# nerdstern.net
KiCad netlist of a schematic drawn in EAGLE
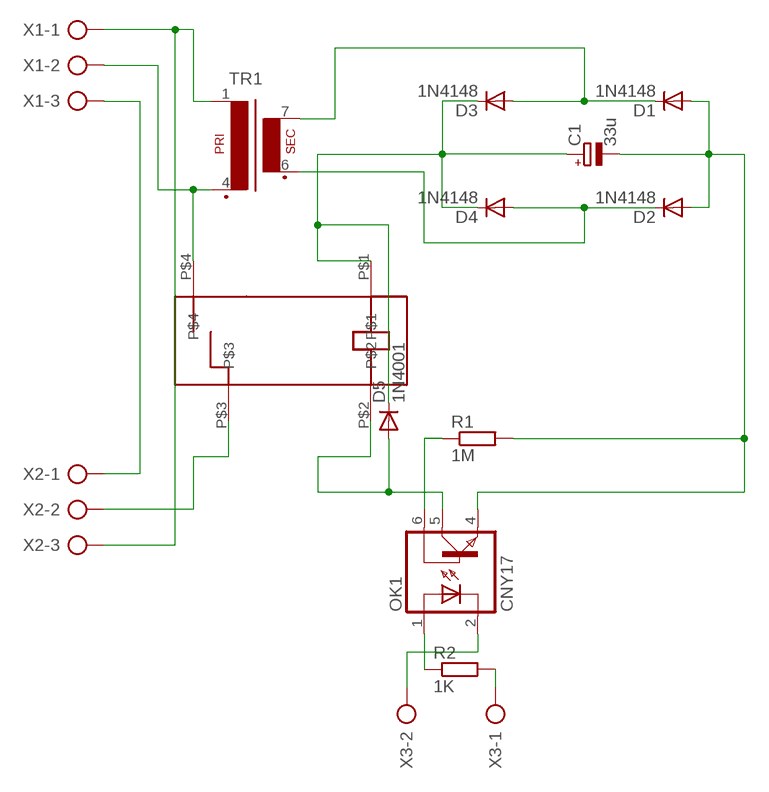
[diagram p0: schematic, sheet 1]

(export (version "E")
  (design (tool "Eeschema 10.0.6"))
  (components
    (comp (ref "C1")
      (value "33u")
      (footprint "eagle-import:E2-5")
      (libsource (lib "eagle-import") (part "CPOL-EUE2-5"))
    )
    (comp (ref "D1")
      (value "1N4148")
      (footprint "eagle-import:DO35-7")
      (libsource (lib "eagle-import") (part "1N4148DO35-7"))
    )
    (comp (ref "D2")
      (value "1N4148")
      (footprint "eagle-import:DO35-7")
      (libsource (lib "eagle-import") (part "1N4148DO35-7"))
    )
    (comp (ref "D3")
      (value "1N4148")
      (footprint "eagle-import:DO35-7")
      (libsource (lib "eagle-import") (part "1N4148DO35-7"))
    )
    (comp (ref "D4")
      (value "1N4148")
      (footprint "eagle-import:DO35-7")
      (libsource (lib "eagle-import") (part "1N4148DO35-7"))
    )
    (comp (ref "D5")
      (value "1N4001")
      (footprint "eagle-import:DO35-7")
      (libsource (lib "eagle-import") (part "1N4148DO35-7"))
    )
    (comp (ref "OK1")
      (value "CNY17")
      (footprint "eagle-import:DIL06")
      (fields (field (name "MPN") "CNY17-1"))
      (libsource (lib "eagle-import") (part "CNY17"))
    )
    (comp (ref "R1")
      (value "1M")
      (footprint "eagle-import:0204_5")
      (libsource (lib "eagle-import") (part "R-EU_0204/5"))
    )
    (comp (ref "R2")
      (value "1K")
      (footprint "eagle-import:0204_5")
      (libsource (lib "eagle-import") (part "R-EU_0204/5"))
    )
    (comp (ref "TR1")
      (value "EE20-1")
      (footprint "eagle-import:EE20-1")
      (libsource (lib "eagle-import") (part "EE20-1"))
    )
    (comp (ref "U$1")
      (value "JS_05_MN_KT")
      (footprint "eagle-import:JS_05_MN_KT")
      (libsource (lib "eagle-import") (part "JS_05_MN_KT"))
    )
    (comp (ref "X1")
      (value "AK500/3")
      (footprint "eagle-import:AK500_3")
      (libsource (lib "eagle-import") (part "AK500/3"))
    )
    (comp (ref "X2")
      (value "AK500/3")
      (footprint "eagle-import:AK500_3")
      (libsource (lib "eagle-import") (part "AK500/3"))
    )
    (comp (ref "X3")
      (value "AK500/2")
      (footprint "eagle-import:AK500_2")
      (libsource (lib "eagle-import") (part "AK500/2"))
    )
  )
  (nets
    (net (code "1") (name "Net-(C1-Pad+)") (class "Default")
      (node (ref "C1") (pin "+") (pinfunction "+_+") (pintype "passive"))
      (node (ref "D3") (pin "C") (pinfunction "C_C") (pintype "passive"))
      (node (ref "D4") (pin "C") (pinfunction "C_C") (pintype "passive"))
      (node (ref "D5") (pin "C") (pinfunction "C_C") (pintype "passive"))
      (node (ref "U$1") (pin "P$1") (pinfunction "P$1_P$1") (pintype "bidirectional"))
    )
    (net (code "2") (name "Net-(OK1-A)") (class "Default")
      (node (ref "OK1") (pin "1") (pinfunction "A_1") (pintype "passive"))
      (node (ref "R2") (pin "1") (pinfunction "1_1") (pintype "passive"))
    )
    (net (code "3") (name "Net-(OK1-BAS)") (class "Default")
      (node (ref "OK1") (pin "6") (pinfunction "BAS_6") (pintype "passive"))
      (node (ref "R1") (pin "1") (pinfunction "1_1") (pintype "passive"))
    )
    (net (code "4") (name "Net-(OK1-C)") (class "Default")
      (node (ref "OK1") (pin "2") (pinfunction "C_2") (pintype "passive"))
      (node (ref "X3") (pin "2") (pinfunction "KL_2") (pintype "passive"))
    )
    (net (code "5") (name "Net-(OK1-COL)") (class "Default")
      (node (ref "D5") (pin "A") (pinfunction "A_A") (pintype "passive"))
      (node (ref "OK1") (pin "5") (pinfunction "COL_5") (pintype "passive"))
      (node (ref "U$1") (pin "P$2") (pinfunction "P$2_P$2") (pintype "bidirectional"))
    )
    (net (code "6") (name "Net-(OK1-EMI)") (class "Default")
      (node (ref "C1") (pin "-") (pinfunction "-_-") (pintype "passive"))
      (node (ref "D1") (pin "A") (pinfunction "A_A") (pintype "passive"))
      (node (ref "D2") (pin "A") (pinfunction "A_A") (pintype "passive"))
      (node (ref "OK1") (pin "4") (pinfunction "EMI_4") (pintype "passive"))
      (node (ref "R1") (pin "2") (pinfunction "2_2") (pintype "passive"))
    )
    (net (code "7") (name "Net-(TR1-P1)") (class "Default")
      (node (ref "TR1") (pin "1") (pinfunction "P1_1") (pintype "passive"))
      (node (ref "X1") (pin "1") (pinfunction "KL_1") (pintype "passive"))
      (node (ref "X2") (pin "3") (pinfunction "KL_3") (pintype "passive"))
    )
    (net (code "8") (name "Net-(TR1-P2)") (class "Default")
      (node (ref "TR1") (pin "4") (pinfunction "P2_4") (pintype "passive"))
      (node (ref "U$1") (pin "P$4") (pinfunction "P$4_P$4") (pintype "bidirectional"))
      (node (ref "X1") (pin "2") (pinfunction "KL_2") (pintype "passive"))
    )
    (net (code "9") (name "Net-(TR1-S3)") (class "Default")
      (node (ref "D2") (pin "C") (pinfunction "C_C") (pintype "passive"))
      (node (ref "D4") (pin "A") (pinfunction "A_A") (pintype "passive"))
      (node (ref "TR1") (pin "6") (pinfunction "S3_6") (pintype "passive"))
    )
    (net (code "10") (name "Net-(TR1-S4)") (class "Default")
      (node (ref "D1") (pin "C") (pinfunction "C_C") (pintype "passive"))
      (node (ref "D3") (pin "A") (pinfunction "A_A") (pintype "passive"))
      (node (ref "TR1") (pin "7") (pinfunction "S4_7") (pintype "passive"))
    )
    (net (code "11") (name "Net-(X1C-KL)") (class "Default")
      (node (ref "X1") (pin "3") (pinfunction "KL_3") (pintype "passive"))
      (node (ref "X2") (pin "1") (pinfunction "KL_1") (pintype "passive"))
    )
    (net (code "12") (name "Net-(X2B-KL)") (class "Default")
      (node (ref "U$1") (pin "P$3") (pinfunction "P$3_P$3") (pintype "bidirectional"))
      (node (ref "X2") (pin "2") (pinfunction "KL_2") (pintype "passive"))
    )
    (net (code "13") (name "Net-(X3A-KL)") (class "Default")
      (node (ref "R2") (pin "2") (pinfunction "2_2") (pintype "passive"))
      (node (ref "X3") (pin "1") (pinfunction "KL_1") (pintype "passive"))
    )
  )
)
